# schematic.net
KiCad netlist of a schematic drawn in Altium Designer
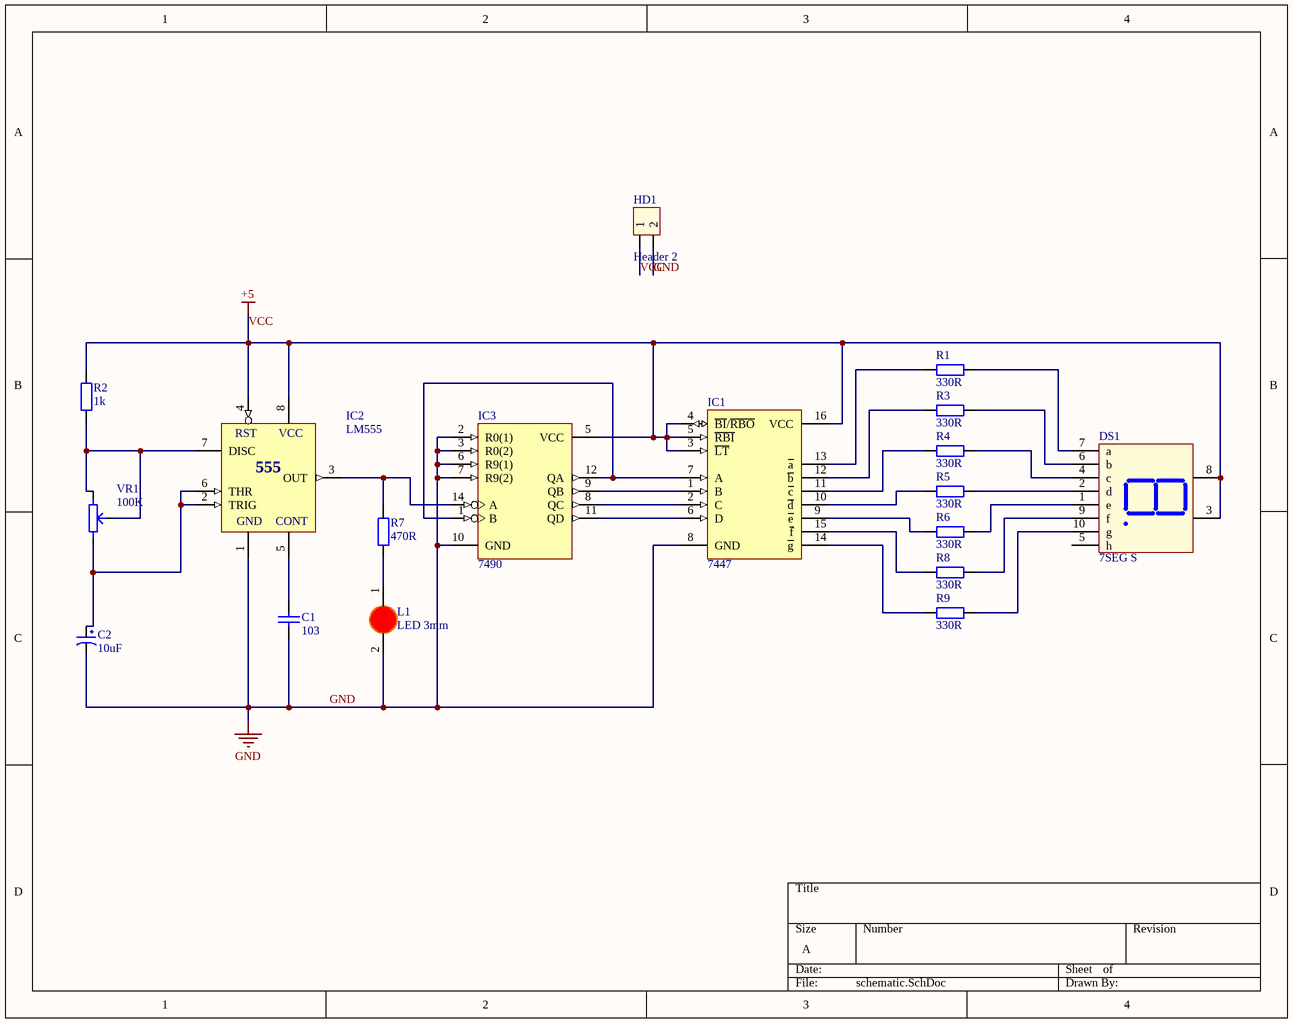
[diagram p0: schematic.SchDoc]

(export (version "E")
  (design (tool "Eeschema 10.0.6"))
  (components
    (comp (ref "C1")
      (value "103")
      (footprint "tu gom")
      (description "Cắm")
      (libsource (lib "Capacitor") (part "Tu gom 103 50V"))
    )
    (comp (ref "C2")
      (value "10uF")
      (footprint "tu hoa 13mm")
      (description "Cắm")
      (libsource (lib "Capacitor") (part "Tu Hoa 10uF 450V 13x20"))
    )
    (comp (ref "DS1")
      (value "7SEG S")
      (footprint "7SEGS")
      (description "Single 7 Seg Dipslay")
      (libsource (lib "syhaunguyen") (part "LED7S"))
    )
    (comp (ref "HD1")
      (value "Header 2")
      (footprint "HED2")
      (description "Header 2 (Green)")
      (libsource (lib "syhaunguyen") (part "Hed2"))
    )
    (comp (ref "IC1")
      (value "7447")
      (footprint "DIP16/W0.3")
      (description "BCD to 7-Segment Decoder/Driver")
      (libsource (lib "My Library") (part "7447"))
    )
    (comp (ref "IC2")
      (value "LM555")
      (footprint "DIP8/W0.3")
      (description "Timer")
      (libsource (lib "My Library") (part "LM555"))
    )
    (comp (ref "IC3")
      (value "7490")
      (footprint "DIP14/W0.3")
      (description "4-Bit Decade Counter")
      (libsource (lib "My Library") (part "7490"))
    )
    (comp (ref "L1")
      (value "LED 3mm")
      (footprint "LED-3MM-RED")
      (description "Cắm")
      (libsource (lib "Led") (part "LED 3mm Do"))
    )
    (comp (ref "R1")
      (value "330R")
      (footprint "tro vach 1/4w")
      (description "Cắm")
      (libsource (lib "Resistor") (part "Tro Vach 1/4W 1% 330R"))
    )
    (comp (ref "R2")
      (value "1k")
      (footprint "tro vach 1/4w")
      (description "Cắm")
      (libsource (lib "Resistor") (part "Tro Vach 1/4W 5% 1k"))
    )
    (comp (ref "R3")
      (value "330R")
      (footprint "tro vach 1/4w")
      (description "Cắm")
      (libsource (lib "Resistor") (part "Tro Vach 1/4W 1% 330R"))
    )
    (comp (ref "R4")
      (value "330R")
      (footprint "tro vach 1/4w")
      (description "Cắm")
      (libsource (lib "Resistor") (part "Tro Vach 1/4W 1% 330R"))
    )
    (comp (ref "R5")
      (value "330R")
      (footprint "tro vach 1/4w")
      (description "Cắm")
      (libsource (lib "Resistor") (part "Tro Vach 1/4W 1% 330R"))
    )
    (comp (ref "R6")
      (value "330R")
      (footprint "tro vach 1/4w")
      (description "Cắm")
      (libsource (lib "Resistor") (part "Tro Vach 1/4W 1% 330R"))
    )
    (comp (ref "R7")
      (value "470R")
      (footprint "tro vach 1/4w")
      (description "Cắm")
      (libsource (lib "Resistor") (part "Tro Vach 1/4W 5% 470R"))
    )
    (comp (ref "R8")
      (value "330R")
      (footprint "tro vach 1/4w")
      (description "Cắm")
      (libsource (lib "Resistor") (part "Tro Vach 1/4W 1% 330R"))
    )
    (comp (ref "R9")
      (value "330R")
      (footprint "tro vach 1/4w")
      (description "Cắm")
      (libsource (lib "Resistor") (part "Tro Vach 1/4W 1% 330R"))
    )
    (comp (ref "VR1")
      (value "100K")
      (footprint "Bien Tro Tam Giac Dung")
      (description "Cắm")
      (libsource (lib "Resistor") (part "Bien tro tam giac 100K Dung"))
    )
  )
  (nets
    (net (code "1") (name "+5") (class "Default")
      (node (ref "DS1") (pin "3") (pinfunction "Vcc_3") (pintype "passive"))
      (node (ref "DS1") (pin "8") (pinfunction "Vcc_8") (pintype "passive"))
      (node (ref "HD1") (pin "1") (pinfunction "1_1") (pintype "passive"))
      (node (ref "IC1") (pin "16") (pinfunction "VCC_16") (pintype "power_in"))
      (node (ref "IC1") (pin "3") (pinfunction "~{LT}_3") (pintype "input"))
      (node (ref "IC1") (pin "4") (pinfunction "~{BI}/~{RBO}_4") (pintype "bidirectional"))
      (node (ref "IC1") (pin "5") (pinfunction "~{RBI}_5") (pintype "input"))
      (node (ref "IC2") (pin "4") (pinfunction "RST_4") (pintype "input"))
      (node (ref "IC2") (pin "8") (pinfunction "VCC_8") (pintype "power_in"))
      (node (ref "IC3") (pin "5") (pinfunction "VCC_5") (pintype "power_in"))
      (node (ref "R2") (pin "2") (pinfunction "2_2") (pintype "passive"))
    )
    (net (code "2") (name "GND") (class "Default")
      (node (ref "C1") (pin "2") (pinfunction "2_2") (pintype "passive"))
      (node (ref "C2") (pin "2") (pinfunction "2_2") (pintype "passive"))
      (node (ref "HD1") (pin "2") (pinfunction "2_2") (pintype "passive"))
      (node (ref "IC1") (pin "8") (pinfunction "GND_8") (pintype "power_in"))
      (node (ref "IC2") (pin "1") (pinfunction "GND_1") (pintype "power_in"))
      (node (ref "IC3") (pin "10") (pinfunction "GND_10") (pintype "power_in"))
      (node (ref "IC3") (pin "2") (pinfunction "R0(1)_2") (pintype "input"))
      (node (ref "IC3") (pin "3") (pinfunction "R0(2)_3") (pintype "input"))
      (node (ref "IC3") (pin "6") (pinfunction "R9(1)_6") (pintype "input"))
      (node (ref "IC3") (pin "7") (pinfunction "R9(2)_7") (pintype "input"))
      (node (ref "L1") (pin "2") (pinfunction "K_2") (pintype "passive"))
    )
    (net (code "3") (name "Net-(DS1-a)") (class "Default")
      (node (ref "DS1") (pin "7") (pinfunction "a_7") (pintype "passive"))
      (node (ref "R1") (pin "2") (pinfunction "2_2") (pintype "passive"))
    )
    (net (code "4") (name "Net-(DS1-b)") (class "Default")
      (node (ref "DS1") (pin "6") (pinfunction "b_6") (pintype "passive"))
      (node (ref "R3") (pin "2") (pinfunction "2_2") (pintype "passive"))
    )
    (net (code "5") (name "Net-(DS1-c)") (class "Default")
      (node (ref "DS1") (pin "4") (pinfunction "c_4") (pintype "passive"))
      (node (ref "R4") (pin "2") (pinfunction "2_2") (pintype "passive"))
    )
    (net (code "6") (name "Net-(DS1-d)") (class "Default")
      (node (ref "DS1") (pin "2") (pinfunction "d_2") (pintype "passive"))
      (node (ref "R5") (pin "2") (pinfunction "2_2") (pintype "passive"))
    )
    (net (code "7") (name "Net-(DS1-e)") (class "Default")
      (node (ref "DS1") (pin "1") (pinfunction "e_1") (pintype "passive"))
      (node (ref "R6") (pin "2") (pinfunction "2_2") (pintype "passive"))
    )
    (net (code "8") (name "Net-(DS1-f)") (class "Default")
      (node (ref "DS1") (pin "9") (pinfunction "f_9") (pintype "passive"))
      (node (ref "R8") (pin "2") (pinfunction "2_2") (pintype "passive"))
    )
    (net (code "9") (name "Net-(DS1-g)") (class "Default")
      (node (ref "DS1") (pin "10") (pinfunction "g_10") (pintype "passive"))
      (node (ref "R9") (pin "2") (pinfunction "2_2") (pintype "passive"))
    )
    (net (code "10") (name "Net-(IC1-A)") (class "Default")
      (node (ref "IC1") (pin "7") (pinfunction "A_7") (pintype "input"))
      (node (ref "IC3") (pin "1") (pinfunction "B_1") (pintype "input"))
      (node (ref "IC3") (pin "12") (pinfunction "QA_12") (pintype "output"))
    )
    (net (code "11") (name "Net-(IC1-B)") (class "Default")
      (node (ref "IC1") (pin "1") (pinfunction "B_1") (pintype "input"))
      (node (ref "IC3") (pin "9") (pinfunction "QB_9") (pintype "output"))
    )
    (net (code "12") (name "Net-(IC1-C)") (class "Default")
      (node (ref "IC1") (pin "2") (pinfunction "C_2") (pintype "input"))
      (node (ref "IC3") (pin "8") (pinfunction "QC_8") (pintype "output"))
    )
    (net (code "13") (name "Net-(IC1-D)") (class "Default")
      (node (ref "IC1") (pin "6") (pinfunction "D_6") (pintype "input"))
      (node (ref "IC3") (pin "11") (pinfunction "QD_11") (pintype "output"))
    )
    (net (code "14") (name "Net-(IC1-~{a})") (class "Default")
      (node (ref "IC1") (pin "13") (pinfunction "~{a}_13") (pintype "open_collector"))
      (node (ref "R1") (pin "1") (pinfunction "1_1") (pintype "passive"))
    )
    (net (code "15") (name "Net-(IC1-~{b})") (class "Default")
      (node (ref "IC1") (pin "12") (pinfunction "~{b}_12") (pintype "open_collector"))
      (node (ref "R3") (pin "1") (pinfunction "1_1") (pintype "passive"))
    )
    (net (code "16") (name "Net-(IC1-~{c})") (class "Default")
      (node (ref "IC1") (pin "11") (pinfunction "~{c}_11") (pintype "open_collector"))
      (node (ref "R4") (pin "1") (pinfunction "1_1") (pintype "passive"))
    )
    (net (code "17") (name "Net-(IC1-~{d})") (class "Default")
      (node (ref "IC1") (pin "10") (pinfunction "~{d}_10") (pintype "open_collector"))
      (node (ref "R5") (pin "1") (pinfunction "1_1") (pintype "passive"))
    )
    (net (code "18") (name "Net-(IC1-~{e})") (class "Default")
      (node (ref "IC1") (pin "9") (pinfunction "~{e}_9") (pintype "open_collector"))
      (node (ref "R6") (pin "1") (pinfunction "1_1") (pintype "passive"))
    )
    (net (code "19") (name "Net-(IC1-~{f})") (class "Default")
      (node (ref "IC1") (pin "15") (pinfunction "~{f}_15") (pintype "open_collector"))
      (node (ref "R8") (pin "1") (pinfunction "1_1") (pintype "passive"))
    )
    (net (code "20") (name "Net-(IC1-~{g})") (class "Default")
      (node (ref "IC1") (pin "14") (pinfunction "~{g}_14") (pintype "open_collector"))
      (node (ref "R9") (pin "1") (pinfunction "1_1") (pintype "passive"))
    )
    (net (code "21") (name "Net-(IC2-CONT)") (class "Default")
      (node (ref "C1") (pin "1") (pinfunction "1_1") (pintype "passive"))
      (node (ref "IC2") (pin "5") (pinfunction "CONT_5") (pintype "passive"))
    )
    (net (code "22") (name "Net-(IC2-DISC)") (class "Default")
      (node (ref "IC2") (pin "7") (pinfunction "DISC_7") (pintype "open_collector"))
      (node (ref "R2") (pin "1") (pinfunction "1_1") (pintype "passive"))
      (node (ref "VR1") (pin "1") (pinfunction "1_1") (pintype "passive"))
      (node (ref "VR1") (pin "2") (pinfunction "2_2") (pintype "passive"))
    )
    (net (code "23") (name "Net-(IC2-OUT)") (class "Default")
      (node (ref "IC2") (pin "3") (pinfunction "OUT_3") (pintype "output"))
      (node (ref "IC3") (pin "14") (pinfunction "A_14") (pintype "input"))
      (node (ref "R7") (pin "2") (pinfunction "2_2") (pintype "passive"))
    )
    (net (code "24") (name "Net-(IC2-THR)") (class "Default")
      (node (ref "C2") (pin "1") (pinfunction "1_1") (pintype "passive"))
      (node (ref "IC2") (pin "2") (pinfunction "TRIG_2") (pintype "input"))
      (node (ref "IC2") (pin "6") (pinfunction "THR_6") (pintype "input"))
      (node (ref "VR1") (pin "3") (pinfunction "3_3") (pintype "passive"))
    )
    (net (code "25") (name "Net-(L1-A)") (class "Default")
      (node (ref "L1") (pin "1") (pinfunction "A_1") (pintype "passive"))
      (node (ref "R7") (pin "1") (pinfunction "1_1") (pintype "passive"))
    )
    (net (code "26") (name "unconnected-(DS1-h-Pad5)") (class "Default")
      (node (ref "DS1") (pin "5") (pinfunction "h_5") (pintype "passive"))
    )
  )
)
